# drobithotshoe_v2_2.net
KiCad netlist of a schematic drawn in EAGLE
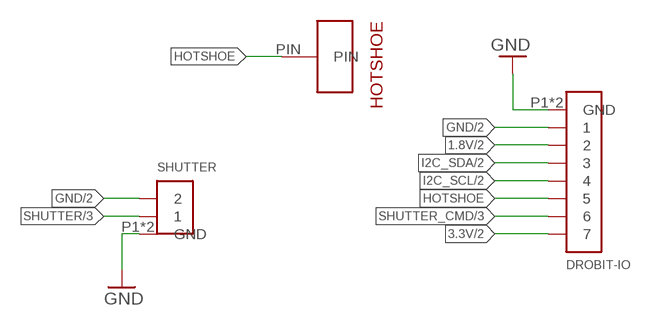
[diagram p0: schematic, sheet 1]
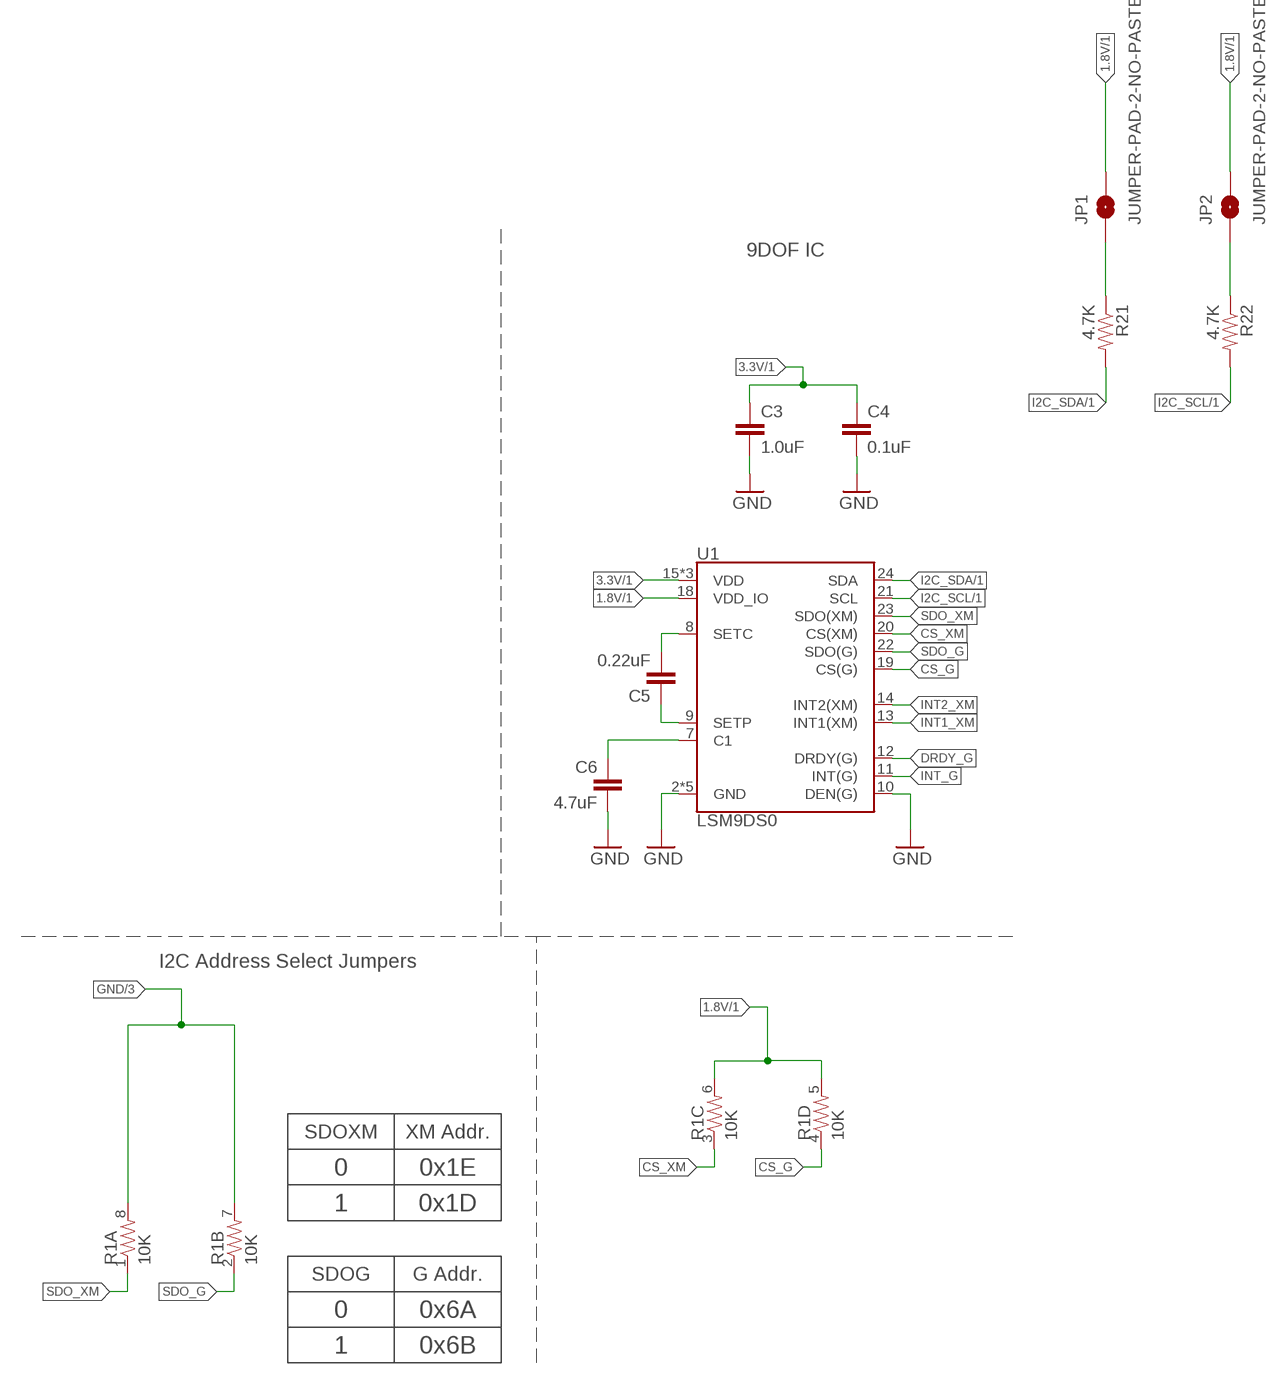
[diagram p1: schematic, sheet 2]
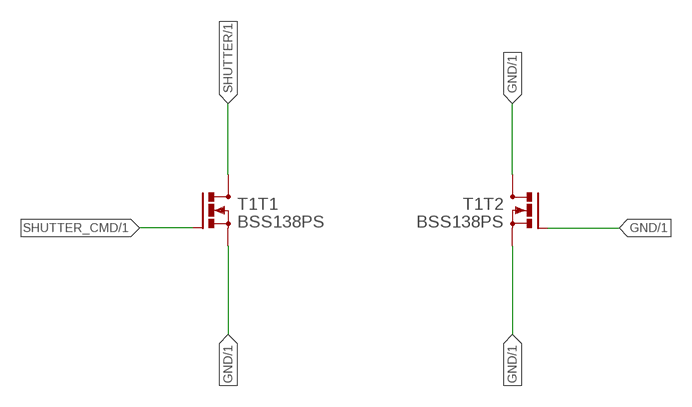
[diagram p2: schematic, sheet 3]

(export (version "E")
  (design (tool "Eeschema 10.0.6"))
  (components
    (comp (ref "C3")
      (value "1.0uF")
      (footprint "eagle-import:0603-CAP")
      (fields (field (name "PARTNO") "810-CGA3E1X7R1E105K"))
      (libsource (lib "eagle-import") (part "1.0UF-16V-10%(0603)"))
    )
    (comp (ref "C4")
      (value "0.1uF")
      (footprint "eagle-import:0603-CAP")
      (fields (field (name "PARTNO") "810-CGA3E2X7R1E104K"))
      (libsource (lib "eagle-import") (part "0.1UF-25V(+80/-20%)(0603)"))
    )
    (comp (ref "C5")
      (value "0.22uF")
      (footprint "eagle-import:0603-CAP")
      (fields (field (name "PARTNO") "810-C1608X7R1C224K"))
      (libsource (lib "eagle-import") (part "0.22UF-16V-10%(0603)"))
    )
    (comp (ref "C6")
      (value "4.7uF")
      (footprint "eagle-import:0603-CAP")
      (fields (field (name "PARTNO") "81-GRM18R60J475KE19D"))
      (libsource (lib "eagle-import") (part "4.7UF-6.3V-10%(0603)0603"))
    )
    (comp (ref "JP1")
      (value "JUMPER-PAD-2-NO-PASTE")
      (footprint "eagle-import:PAD-JUMPER-2-NO_NO_SILK_PASTE")
      (libsource (lib "eagle-import") (part "JUMPER-PAD-2-NO-PASTE"))
    )
    (comp (ref "JP2")
      (value "JUMPER-PAD-2-NO-PASTE")
      (footprint "eagle-import:PAD-JUMPER-2-NO_NO_SILK_PASTE")
      (libsource (lib "eagle-import") (part "JUMPER-PAD-2-NO-PASTE"))
    )
    (comp (ref "R1")
      (value "10K")
      (footprint "eagle-import:0603-ARV")
      (fields (field (name "PARTNO") "667-EXB-38V103JV"))
      (libsource (lib "eagle-import") (part "RESISTOR-ARRAY0603-ARV"))
    )
    (comp (ref "R21")
      (value "4.7K")
      (footprint "eagle-import:0603-RES")
      (fields (field (name "PARTNO") "667-ERJ-3GEYJ472V"))
      (libsource (lib "eagle-import") (part "4.7KOHM-1/10W-1%(0603)"))
    )
    (comp (ref "R22")
      (value "4.7K")
      (footprint "eagle-import:0603-RES")
      (fields (field (name "PARTNO") "667-ERJ-3GEYJ472V"))
      (libsource (lib "eagle-import") (part "4.7KOHM-1/10W-1%(0603)"))
    )
    (comp (ref "U1")
      (value "LSM9DS0")
      (footprint "eagle-import:LGA-24")
      (fields (field (name "PARTNO") "497-13902-1-ND"))
      (libsource (lib "eagle-import") (part "LSM9DS0"))
    )
    (comp (ref "DROBIT-IO")
      (value "CONN_7-1")
      (footprint "eagle-import:JST-GH-7")
      (fields (field (name "PARTNO") "455-1569-1-ND"))
      (libsource (lib "eagle-import") (part "CONN_7-1"))
    )
    (comp (ref "HOTSHOE")
      (value "ZAPATA-MILMAX")
      (footprint "eagle-import:MILMAX-807-22-001-30-000101")
      (fields (field (name "PARTNO") "NO_PONER"))
      (libsource (lib "eagle-import") (part "ZAPATA-MILMAX"))
    )
    (comp (ref "SHUTTER")
      (value "CONN_2-1-GH-VERT")
      (footprint "eagle-import:JST-GH-2-V")
      (fields (field (name "PARTNO") "455-1564-1-ND"))
      (libsource (lib "eagle-import") (part "CONN_2-1-GH-VERT"))
    )
    (comp (ref "T1")
      (value "BSS138PS")
      (footprint "eagle-import:SOT363")
      (fields (field (name "MF") "NXP Semiconductors") (field (name "PARTNO") "771-BSS138BKS115"))
      (libsource (lib "eagle-import") (part "BSS138PS"))
    )
  )
  (nets
    (net (code "1") (name "1.8V") (class "Default")
      (node (ref "DROBIT-IO") (pin "2") (pinfunction "2_2") (pintype "bidirectional"))
      (node (ref "JP1") (pin "2") (pinfunction "2_2") (pintype "passive"))
      (node (ref "JP2") (pin "2") (pinfunction "2_2") (pintype "passive"))
      (node (ref "R1") (pin "5") (pinfunction "2_5") (pintype "passive"))
      (node (ref "R1") (pin "6") (pinfunction "2_6") (pintype "passive"))
      (node (ref "U1") (pin "18") (pinfunction "VDD_IO_18") (pintype "bidirectional"))
    )
    (net (code "2") (name "3.3V") (class "Default")
      (node (ref "C3") (pin "1") (pinfunction "1_1") (pintype "passive"))
      (node (ref "C4") (pin "1") (pinfunction "1_1") (pintype "passive"))
      (node (ref "DROBIT-IO") (pin "7") (pinfunction "7_7") (pintype "bidirectional"))
      (node (ref "U1") (pin "15") (pinfunction "VDD_15") (pintype "bidirectional"))
      (node (ref "U1") (pin "16") (pinfunction "VDD_16") (pintype "bidirectional"))
      (node (ref "U1") (pin "17") (pinfunction "VDD_17") (pintype "bidirectional"))
    )
    (net (code "3") (name "CS_G") (class "Default")
      (node (ref "R1") (pin "4") (pinfunction "1_4") (pintype "passive"))
      (node (ref "U1") (pin "19") (pinfunction "CS(G)_19") (pintype "bidirectional"))
    )
    (net (code "4") (name "CS_XM") (class "Default")
      (node (ref "R1") (pin "3") (pinfunction "1_3") (pintype "passive"))
      (node (ref "U1") (pin "20") (pinfunction "CS(XM)_20") (pintype "bidirectional"))
    )
    (net (code "5") (name "DRDY_G") (class "Default")
      (node (ref "U1") (pin "12") (pinfunction "DRDY(G)_12") (pintype "bidirectional"))
    )
    (net (code "6") (name "GND") (class "Default")
      (node (ref "C3") (pin "2") (pinfunction "2_2") (pintype "passive"))
      (node (ref "C4") (pin "2") (pinfunction "2_2") (pintype "passive"))
      (node (ref "C6") (pin "2") (pinfunction "2_2") (pintype "passive"))
      (node (ref "DROBIT-IO") (pin "1") (pinfunction "1_1") (pintype "bidirectional"))
      (node (ref "DROBIT-IO") (pin "P1") (pinfunction "GND_P1") (pintype "bidirectional"))
      (node (ref "DROBIT-IO") (pin "P2") (pinfunction "GND_P2") (pintype "bidirectional"))
      (node (ref "R1") (pin "7") (pinfunction "2_7") (pintype "passive"))
      (node (ref "R1") (pin "8") (pinfunction "2_8") (pintype "passive"))
      (node (ref "SHUTTER") (pin "2") (pinfunction "2_2") (pintype "bidirectional"))
      (node (ref "SHUTTER") (pin "P1") (pinfunction "GND_P1") (pintype "bidirectional"))
      (node (ref "SHUTTER") (pin "P2") (pinfunction "GND_P2") (pintype "bidirectional"))
      (node (ref "T1") (pin "1") (pinfunction "S_1") (pintype "passive"))
      (node (ref "T1") (pin "3") (pinfunction "D_3") (pintype "passive"))
      (node (ref "T1") (pin "4") (pinfunction "S_4") (pintype "passive"))
      (node (ref "T1") (pin "5") (pinfunction "G_5") (pintype "passive"))
      (node (ref "U1") (pin "10") (pinfunction "DEN(G)_10") (pintype "bidirectional"))
      (node (ref "U1") (pin "2") (pinfunction "GND_2") (pintype "bidirectional"))
      (node (ref "U1") (pin "3") (pinfunction "GND_3") (pintype "bidirectional"))
      (node (ref "U1") (pin "4") (pinfunction "GND_4") (pintype "bidirectional"))
      (node (ref "U1") (pin "5") (pinfunction "GND_5") (pintype "bidirectional"))
      (node (ref "U1") (pin "6") (pinfunction "GND_6") (pintype "bidirectional"))
    )
    (net (code "7") (name "HOTSHOE") (class "Default")
      (node (ref "DROBIT-IO") (pin "5") (pinfunction "5_5") (pintype "bidirectional"))
      (node (ref "HOTSHOE") (pin "PIN") (pinfunction "PIN_PIN") (pintype "bidirectional"))
    )
    (net (code "8") (name "I2C_SCL") (class "Default")
      (node (ref "DROBIT-IO") (pin "4") (pinfunction "4_4") (pintype "bidirectional"))
      (node (ref "R22") (pin "2") (pinfunction "2_2") (pintype "passive"))
      (node (ref "U1") (pin "21") (pinfunction "SCL_21") (pintype "bidirectional"))
    )
    (net (code "9") (name "I2C_SDA") (class "Default")
      (node (ref "DROBIT-IO") (pin "3") (pinfunction "3_3") (pintype "bidirectional"))
      (node (ref "R21") (pin "2") (pinfunction "2_2") (pintype "passive"))
      (node (ref "U1") (pin "24") (pinfunction "SDA_24") (pintype "bidirectional"))
    )
    (net (code "10") (name "INT1_XM") (class "Default")
      (node (ref "U1") (pin "13") (pinfunction "INT1(XM)_13") (pintype "bidirectional"))
    )
    (net (code "11") (name "INT2_XM") (class "Default")
      (node (ref "U1") (pin "14") (pinfunction "INT2(XM)_14") (pintype "bidirectional"))
    )
    (net (code "12") (name "INT_G") (class "Default")
      (node (ref "U1") (pin "11") (pinfunction "INT(G)_11") (pintype "bidirectional"))
    )
    (net (code "13") (name "Net-(JP1-Pad1)") (class "Default")
      (node (ref "JP1") (pin "1") (pinfunction "1_1") (pintype "passive"))
      (node (ref "R21") (pin "1") (pinfunction "1_1") (pintype "passive"))
    )
    (net (code "14") (name "Net-(JP2-Pad1)") (class "Default")
      (node (ref "JP2") (pin "1") (pinfunction "1_1") (pintype "passive"))
      (node (ref "R22") (pin "1") (pinfunction "1_1") (pintype "passive"))
    )
    (net (code "15") (name "Net-(U1-C1)") (class "Default")
      (node (ref "C6") (pin "1") (pinfunction "1_1") (pintype "passive"))
      (node (ref "U1") (pin "7") (pinfunction "C1_7") (pintype "bidirectional"))
    )
    (net (code "16") (name "Net-(U1-SETC)") (class "Default")
      (node (ref "C5") (pin "2") (pinfunction "2_2") (pintype "passive"))
      (node (ref "U1") (pin "8") (pinfunction "SETC_8") (pintype "bidirectional"))
    )
    (net (code "17") (name "Net-(U1-SETP)") (class "Default")
      (node (ref "C5") (pin "1") (pinfunction "1_1") (pintype "passive"))
      (node (ref "U1") (pin "9") (pinfunction "SETP_9") (pintype "bidirectional"))
    )
    (net (code "18") (name "SDO_G") (class "Default")
      (node (ref "R1") (pin "2") (pinfunction "1_2") (pintype "passive"))
      (node (ref "U1") (pin "22") (pinfunction "SDO(G)_22") (pintype "bidirectional"))
    )
    (net (code "19") (name "SDO_XM") (class "Default")
      (node (ref "R1") (pin "1") (pinfunction "1_1") (pintype "passive"))
      (node (ref "U1") (pin "23") (pinfunction "SDO(XM)_23") (pintype "bidirectional"))
    )
    (net (code "20") (name "SHUTTER") (class "Default")
      (node (ref "SHUTTER") (pin "1") (pinfunction "1_1") (pintype "bidirectional"))
      (node (ref "T1") (pin "6") (pinfunction "D_6") (pintype "passive"))
    )
    (net (code "21") (name "SHUTTER_CMD") (class "Default")
      (node (ref "DROBIT-IO") (pin "6") (pinfunction "6_6") (pintype "bidirectional"))
      (node (ref "T1") (pin "2") (pinfunction "G_2") (pintype "passive"))
    )
  )
)
